# PDM-S08-V00-PDMCConnector.net
KiCad netlist of a schematic drawn in Altium Designer
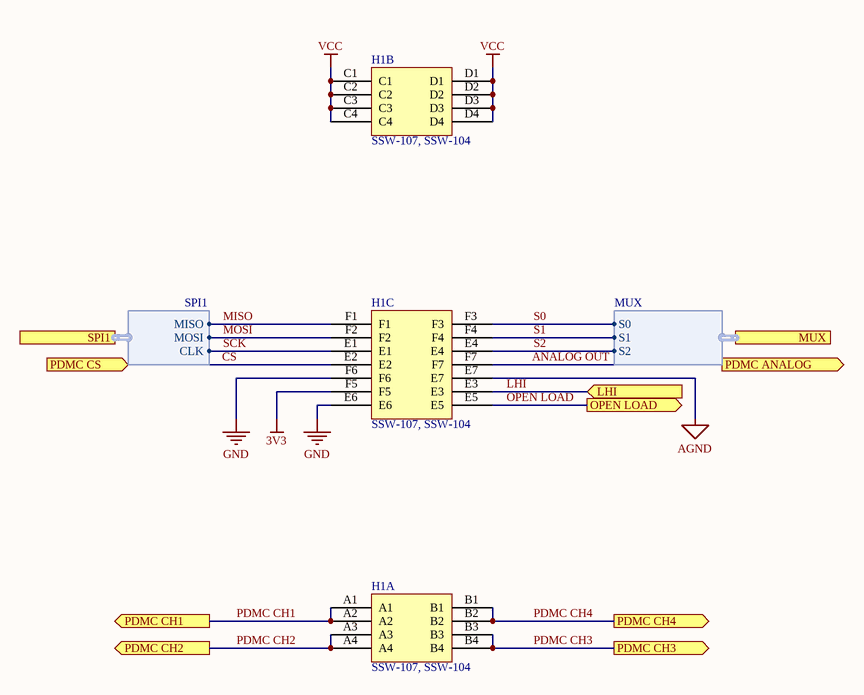
[diagram p0: PDM-S08-V00-PDMCConnector.SchDoc]

(export (version "E")
  (design (tool "Eeschema 10.0.6"))
  (components
    (comp (ref "H1")
      (value "SSW-107, SSW-104")
      (footprint "SSW-107, SSW-104")
      (description "CONN RCPT 8POS, 14POS 0.1 TIN PCB")
      (libsource (lib "SamtecHeader") (part "SSW-107, SSW-104"))
    )
  )
  (nets
    (net (code "3") (name "/ANALOG OUT") (class "Default")
      (node (ref "H1") (pin "F7") (pinfunction "F7_F7") (pintype "passive"))
    )
    (net (code "4") (name "/CS") (class "Default")
      (node (ref "H1") (pin "E2") (pinfunction "E2_E2") (pintype "passive"))
    )
    (net (code "5") (name "/LHI") (class "Default")
      (node (ref "H1") (pin "E3") (pinfunction "E3_E3") (pintype "passive"))
    )
    (net (code "6") (name "/MISO") (class "Default")
      (node (ref "H1") (pin "F1") (pinfunction "F1_F1") (pintype "passive"))
    )
    (net (code "7") (name "/MOSI") (class "Default")
      (node (ref "H1") (pin "F2") (pinfunction "F2_F2") (pintype "passive"))
    )
    (net (code "8") (name "/OPEN LOAD") (class "Default")
      (node (ref "H1") (pin "E5") (pinfunction "E5_E5") (pintype "passive"))
    )
    (net (code "9") (name "/PDMC CH1") (class "Default")
      (node (ref "H1") (pin "A1") (pinfunction "A1_A1") (pintype "passive"))
      (node (ref "H1") (pin "A2") (pinfunction "A2_A2") (pintype "passive"))
    )
    (net (code "10") (name "/PDMC CH2") (class "Default")
      (node (ref "H1") (pin "A3") (pinfunction "A3_A3") (pintype "passive"))
      (node (ref "H1") (pin "A4") (pinfunction "A4_A4") (pintype "passive"))
    )
    (net (code "11") (name "/PDMC CH3") (class "Default")
      (node (ref "H1") (pin "B3") (pinfunction "B3_B3") (pintype "passive"))
      (node (ref "H1") (pin "B4") (pinfunction "B4_B4") (pintype "passive"))
    )
    (net (code "12") (name "/PDMC CH4") (class "Default")
      (node (ref "H1") (pin "B1") (pinfunction "B1_B1") (pintype "passive"))
      (node (ref "H1") (pin "B2") (pinfunction "B2_B2") (pintype "passive"))
    )
    (net (code "13") (name "/S0") (class "Default")
      (node (ref "H1") (pin "F3") (pinfunction "F3_F3") (pintype "passive"))
    )
    (net (code "14") (name "/S1") (class "Default")
      (node (ref "H1") (pin "F4") (pinfunction "F4_F4") (pintype "passive"))
    )
    (net (code "15") (name "/S2") (class "Default")
      (node (ref "H1") (pin "E4") (pinfunction "E4_E4") (pintype "passive"))
    )
    (net (code "16") (name "/SCK") (class "Default")
      (node (ref "H1") (pin "E1") (pinfunction "E1_E1") (pintype "passive"))
    )
    (net (code "19") (name "3V3") (class "Default")
      (node (ref "H1") (pin "F5") (pinfunction "F5_F5") (pintype "passive"))
    )
    (net (code "20") (name "AGND") (class "Default")
      (node (ref "H1") (pin "E7") (pinfunction "E7_E7") (pintype "passive"))
    )
    (net (code "21") (name "GND") (class "Default")
      (node (ref "H1") (pin "E6") (pinfunction "E6_E6") (pintype "passive"))
      (node (ref "H1") (pin "F6") (pinfunction "F6_F6") (pintype "passive"))
    )
    (net (code "22") (name "VCC") (class "Default")
      (node (ref "H1") (pin "C1") (pinfunction "C1_C1") (pintype "passive"))
      (node (ref "H1") (pin "C2") (pinfunction "C2_C2") (pintype "passive"))
      (node (ref "H1") (pin "C3") (pinfunction "C3_C3") (pintype "passive"))
      (node (ref "H1") (pin "C4") (pinfunction "C4_C4") (pintype "passive"))
      (node (ref "H1") (pin "D1") (pinfunction "D1_D1") (pintype "passive"))
      (node (ref "H1") (pin "D2") (pinfunction "D2_D2") (pintype "passive"))
      (node (ref "H1") (pin "D3") (pinfunction "D3_D3") (pintype "passive"))
      (node (ref "H1") (pin "D4") (pinfunction "D4_D4") (pintype "passive"))
    )
  )
)
